# quadripod_v2.net
KiCad netlist of a schematic drawn in EAGLE
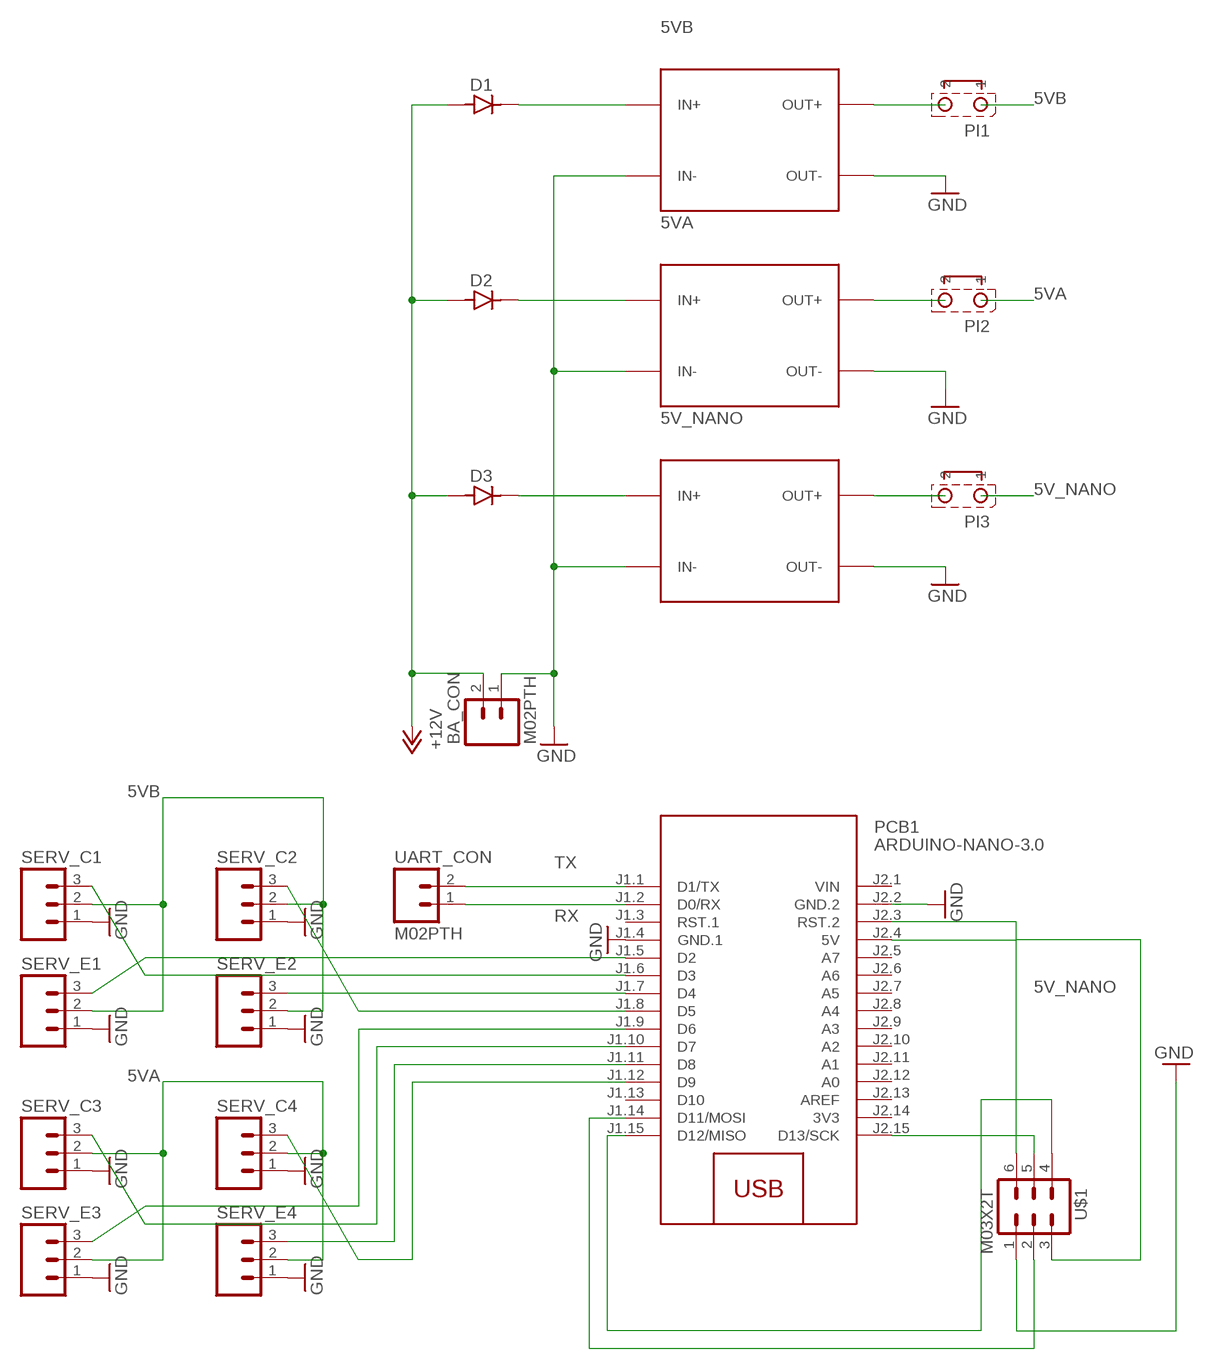
[diagram p0: schematic, sheet 1]

(export (version "E")
  (design (tool "Eeschema 10.0.6"))
  (components
    (comp (ref "5VA")
      (value "DC-DC-STEP-DOWN-LM2596")
      (footprint "eagle-import:DC-DC-STEP-DOWN-LM2596")
      (libsource (lib "eagle-import") (part "DC-DC-STEP-DOWN-LM2596"))
    )
    (comp (ref "5VB")
      (value "DC-DC-STEP-DOWN-LM2596")
      (footprint "eagle-import:DC-DC-STEP-DOWN-LM2596")
      (libsource (lib "eagle-import") (part "DC-DC-STEP-DOWN-LM2596"))
    )
    (comp (ref "5V_NANO")
      (value "DC-DC-STEP-DOWN-LM2596")
      (footprint "eagle-import:DC-DC-STEP-DOWN-LM2596")
      (libsource (lib "eagle-import") (part "DC-DC-STEP-DOWN-LM2596"))
    )
    (comp (ref "BA_CON")
      (value "M02PTH")
      (footprint "eagle-import:1X02")
      (libsource (lib "eagle-import") (part "M02PTH"))
    )
    (comp (ref "D1")
      (value "DIODES_DIODE/DO41")
      (footprint "eagle-import:DIODES_DO41")
      (libsource (lib "eagle-import") (part "DIODES_DIODE/DO41"))
    )
    (comp (ref "D2")
      (value "DIODES_DIODE/DO41")
      (footprint "eagle-import:DIODES_DO41")
      (libsource (lib "eagle-import") (part "DIODES_DIODE/DO41"))
    )
    (comp (ref "D3")
      (value "DIODES_DIODE/DO41")
      (footprint "eagle-import:DIODES_DO41")
      (libsource (lib "eagle-import") (part "DIODES_DIODE/DO41"))
    )
    (comp (ref "PCB1")
      (value "ARDUINO-NANO-3.0")
      (footprint "eagle-import:ARDUINO-NANO-3.0")
      (libsource (lib "eagle-import") (part "ARDUINO-NANO-3.0"))
    )
    (comp (ref "PI1")
      (value "STCMS_2")
      (footprint "eagle-import:STCMS_2")
      (libsource (lib "eagle-import") (part "STCMS_2"))
    )
    (comp (ref "PI2")
      (value "STCMS_2")
      (footprint "eagle-import:STCMS_2")
      (libsource (lib "eagle-import") (part "STCMS_2"))
    )
    (comp (ref "PI3")
      (value "STCMS_2")
      (footprint "eagle-import:STCMS_2")
      (libsource (lib "eagle-import") (part "STCMS_2"))
    )
    (comp (ref "SERV_C1")
      (value "M03LONGPADS")
      (footprint "eagle-import:1X03_LONGPADS")
      (libsource (lib "eagle-import") (part "M03LONGPADS"))
    )
    (comp (ref "SERV_C2")
      (value "M03LONGPADS")
      (footprint "eagle-import:1X03_LONGPADS")
      (libsource (lib "eagle-import") (part "M03LONGPADS"))
    )
    (comp (ref "SERV_C3")
      (value "M03LONGPADS")
      (footprint "eagle-import:1X03_LONGPADS")
      (libsource (lib "eagle-import") (part "M03LONGPADS"))
    )
    (comp (ref "SERV_C4")
      (value "M03LONGPADS")
      (footprint "eagle-import:1X03_LONGPADS")
      (libsource (lib "eagle-import") (part "M03LONGPADS"))
    )
    (comp (ref "SERV_E1")
      (value "M03LONGPADS")
      (footprint "eagle-import:1X03_LONGPADS")
      (libsource (lib "eagle-import") (part "M03LONGPADS"))
    )
    (comp (ref "SERV_E2")
      (value "M03LONGPADS")
      (footprint "eagle-import:1X03_LONGPADS")
      (libsource (lib "eagle-import") (part "M03LONGPADS"))
    )
    (comp (ref "SERV_E3")
      (value "M03LONGPADS")
      (footprint "eagle-import:1X03_LONGPADS")
      (libsource (lib "eagle-import") (part "M03LONGPADS"))
    )
    (comp (ref "SERV_E4")
      (value "M03LONGPADS")
      (footprint "eagle-import:1X03_LONGPADS")
      (libsource (lib "eagle-import") (part "M03LONGPADS"))
    )
    (comp (ref "U$1")
      (value "M03X2T")
      (footprint "eagle-import:2X03")
      (libsource (lib "eagle-import") (part "M03X2T"))
    )
    (comp (ref "UART_CON")
      (value "M02PTH")
      (footprint "eagle-import:1X02")
      (libsource (lib "eagle-import") (part "M02PTH"))
    )
  )
  (nets
    (net (code "1") (name "+12V") (class "Default")
      (node (ref "BA_CON") (pin "2") (pinfunction "2_2") (pintype "passive"))
      (node (ref "D1") (pin "A") (pinfunction "A_A") (pintype "passive"))
      (node (ref "D2") (pin "A") (pinfunction "A_A") (pintype "passive"))
      (node (ref "D3") (pin "A") (pinfunction "A_A") (pintype "passive"))
    )
    (net (code "2") (name "/3V3") (class "Default")
      (node (ref "PCB1") (pin "J2.14") (pinfunction "3V3_J2.14") (pintype "power_in"))
    )
    (net (code "3") (name "/5VA") (class "Default")
      (node (ref "PI2") (pin "1") (pinfunction "1_1") (pintype "bidirectional"))
      (node (ref "SERV_C3") (pin "2") (pinfunction "2_2") (pintype "passive"))
      (node (ref "SERV_C4") (pin "2") (pinfunction "2_2") (pintype "passive"))
      (node (ref "SERV_E3") (pin "2") (pinfunction "2_2") (pintype "passive"))
      (node (ref "SERV_E4") (pin "2") (pinfunction "2_2") (pintype "passive"))
    )
    (net (code "4") (name "/5VB") (class "Default")
      (node (ref "PI1") (pin "1") (pinfunction "1_1") (pintype "bidirectional"))
      (node (ref "SERV_C1") (pin "2") (pinfunction "2_2") (pintype "passive"))
      (node (ref "SERV_C2") (pin "2") (pinfunction "2_2") (pintype "passive"))
      (node (ref "SERV_E1") (pin "2") (pinfunction "2_2") (pintype "passive"))
      (node (ref "SERV_E2") (pin "2") (pinfunction "2_2") (pintype "passive"))
    )
    (net (code "5") (name "/5V_NANO") (class "Default")
      (node (ref "PCB1") (pin "J2.4") (pinfunction "5V_J2.4") (pintype "power_in"))
      (node (ref "PI3") (pin "1") (pinfunction "1_1") (pintype "bidirectional"))
      (node (ref "U$1") (pin "3") (pinfunction "3_3") (pintype "passive"))
    )
    (net (code "6") (name "/RX") (class "Default")
      (node (ref "PCB1") (pin "J1.2") (pinfunction "D0/RX_J1.2") (pintype "bidirectional"))
      (node (ref "UART_CON") (pin "1") (pinfunction "1_1") (pintype "passive"))
    )
    (net (code "7") (name "/TX") (class "Default")
      (node (ref "PCB1") (pin "J1.1") (pinfunction "D1/TX_J1.1") (pintype "bidirectional"))
      (node (ref "UART_CON") (pin "2") (pinfunction "2_2") (pintype "passive"))
    )
    (net (code "8") (name "/VIN") (class "Default")
      (node (ref "PCB1") (pin "J2.1") (pinfunction "VIN_J2.1") (pintype "power_in"))
    )
    (net (code "9") (name "GND") (class "Default")
      (node (ref "5VA") (pin "IN-") (pinfunction "IN-_IN-") (pintype "bidirectional"))
      (node (ref "5VA") (pin "OUT-") (pinfunction "OUT-_OUT-") (pintype "bidirectional"))
      (node (ref "5VB") (pin "IN-") (pinfunction "IN-_IN-") (pintype "bidirectional"))
      (node (ref "5VB") (pin "OUT-") (pinfunction "OUT-_OUT-") (pintype "bidirectional"))
      (node (ref "5V_NANO") (pin "IN-") (pinfunction "IN-_IN-") (pintype "bidirectional"))
      (node (ref "5V_NANO") (pin "OUT-") (pinfunction "OUT-_OUT-") (pintype "bidirectional"))
      (node (ref "BA_CON") (pin "1") (pinfunction "1_1") (pintype "passive"))
      (node (ref "PCB1") (pin "J1.4") (pinfunction "GND.1_J1.4") (pintype "power_in"))
      (node (ref "PCB1") (pin "J2.2") (pinfunction "GND.2_J2.2") (pintype "power_in"))
      (node (ref "SERV_C1") (pin "1") (pinfunction "1_1") (pintype "passive"))
      (node (ref "SERV_C2") (pin "1") (pinfunction "1_1") (pintype "passive"))
      (node (ref "SERV_C3") (pin "1") (pinfunction "1_1") (pintype "passive"))
      (node (ref "SERV_C4") (pin "1") (pinfunction "1_1") (pintype "passive"))
      (node (ref "SERV_E1") (pin "1") (pinfunction "1_1") (pintype "passive"))
      (node (ref "SERV_E2") (pin "1") (pinfunction "1_1") (pintype "passive"))
      (node (ref "SERV_E3") (pin "1") (pinfunction "1_1") (pintype "passive"))
      (node (ref "SERV_E4") (pin "1") (pinfunction "1_1") (pintype "passive"))
      (node (ref "U$1") (pin "1") (pinfunction "1_1") (pintype "passive"))
    )
    (net (code "10") (name "Net-(5VA-PadIN+)") (class "Default")
      (node (ref "5VA") (pin "IN+") (pinfunction "IN+_IN+") (pintype "bidirectional"))
      (node (ref "D2") (pin "K") (pinfunction "K_K") (pintype "passive"))
    )
    (net (code "11") (name "Net-(5VA-PadOUT+)") (class "Default")
      (node (ref "5VA") (pin "OUT+") (pinfunction "OUT+_OUT+") (pintype "bidirectional"))
      (node (ref "PI2") (pin "2") (pinfunction "2_2") (pintype "bidirectional"))
    )
    (net (code "12") (name "Net-(5VB-PadIN+)") (class "Default")
      (node (ref "5VB") (pin "IN+") (pinfunction "IN+_IN+") (pintype "bidirectional"))
      (node (ref "D1") (pin "K") (pinfunction "K_K") (pintype "passive"))
    )
    (net (code "13") (name "Net-(5VB-PadOUT+)") (class "Default")
      (node (ref "5VB") (pin "OUT+") (pinfunction "OUT+_OUT+") (pintype "bidirectional"))
      (node (ref "PI1") (pin "2") (pinfunction "2_2") (pintype "bidirectional"))
    )
    (net (code "14") (name "Net-(5V_NANO-PadIN+)") (class "Default")
      (node (ref "5V_NANO") (pin "IN+") (pinfunction "IN+_IN+") (pintype "bidirectional"))
      (node (ref "D3") (pin "K") (pinfunction "K_K") (pintype "passive"))
    )
    (net (code "15") (name "Net-(5V_NANO-PadOUT+)") (class "Default")
      (node (ref "5V_NANO") (pin "OUT+") (pinfunction "OUT+_OUT+") (pintype "bidirectional"))
      (node (ref "PI3") (pin "2") (pinfunction "2_2") (pintype "bidirectional"))
    )
    (net (code "16") (name "Net-(PCB1-D2)") (class "Default")
      (node (ref "PCB1") (pin "J1.5") (pinfunction "D2_J1.5") (pintype "bidirectional"))
      (node (ref "SERV_E1") (pin "3") (pinfunction "3_3") (pintype "passive"))
    )
    (net (code "17") (name "Net-(PCB1-D3)") (class "Default")
      (node (ref "PCB1") (pin "J1.6") (pinfunction "D3_J1.6") (pintype "bidirectional"))
      (node (ref "SERV_C1") (pin "3") (pinfunction "3_3") (pintype "passive"))
    )
    (net (code "18") (name "Net-(PCB1-D4)") (class "Default")
      (node (ref "PCB1") (pin "J1.7") (pinfunction "D4_J1.7") (pintype "bidirectional"))
      (node (ref "SERV_E2") (pin "3") (pinfunction "3_3") (pintype "passive"))
    )
    (net (code "19") (name "Net-(PCB1-D5)") (class "Default")
      (node (ref "PCB1") (pin "J1.8") (pinfunction "D5_J1.8") (pintype "bidirectional"))
      (node (ref "SERV_C2") (pin "3") (pinfunction "3_3") (pintype "passive"))
    )
    (net (code "20") (name "Net-(PCB1-D6)") (class "Default")
      (node (ref "PCB1") (pin "J1.9") (pinfunction "D6_J1.9") (pintype "bidirectional"))
      (node (ref "SERV_E3") (pin "3") (pinfunction "3_3") (pintype "passive"))
    )
    (net (code "21") (name "Net-(PCB1-D7)") (class "Default")
      (node (ref "PCB1") (pin "J1.10") (pinfunction "D7_J1.10") (pintype "bidirectional"))
      (node (ref "SERV_C3") (pin "3") (pinfunction "3_3") (pintype "passive"))
    )
    (net (code "22") (name "Net-(PCB1-D8)") (class "Default")
      (node (ref "PCB1") (pin "J1.11") (pinfunction "D8_J1.11") (pintype "bidirectional"))
      (node (ref "SERV_E4") (pin "3") (pinfunction "3_3") (pintype "passive"))
    )
    (net (code "23") (name "Net-(PCB1-D9)") (class "Default")
      (node (ref "PCB1") (pin "J1.12") (pinfunction "D9_J1.12") (pintype "bidirectional"))
      (node (ref "SERV_C4") (pin "3") (pinfunction "3_3") (pintype "passive"))
    )
    (net (code "24") (name "Net-(PCB1-D11{slash}MOSI)") (class "Default")
      (node (ref "PCB1") (pin "J1.14") (pinfunction "D11/MOSI_J1.14") (pintype "bidirectional"))
      (node (ref "U$1") (pin "2") (pinfunction "2_2") (pintype "passive"))
    )
    (net (code "25") (name "Net-(PCB1-D12{slash}MISO)") (class "Default")
      (node (ref "PCB1") (pin "J1.15") (pinfunction "D12/MISO_J1.15") (pintype "bidirectional"))
      (node (ref "U$1") (pin "4") (pinfunction "4_4") (pintype "passive"))
    )
    (net (code "26") (name "Net-(PCB1-D13{slash}SCK)") (class "Default")
      (node (ref "PCB1") (pin "J2.15") (pinfunction "D13/SCK_J2.15") (pintype "bidirectional"))
      (node (ref "U$1") (pin "5") (pinfunction "5_5") (pintype "passive"))
    )
    (net (code "27") (name "Net-(PCB1-RST.2)") (class "Default")
      (node (ref "PCB1") (pin "J2.3") (pinfunction "RST.2_J2.3") (pintype "bidirectional"))
      (node (ref "U$1") (pin "6") (pinfunction "6_6") (pintype "passive"))
    )
    (net (code "28") (name "unconnected-(PCB1-A0-PadJ2.12)") (class "Default")
      (node (ref "PCB1") (pin "J2.12") (pinfunction "A0_J2.12") (pintype "bidirectional"))
    )
    (net (code "29") (name "unconnected-(PCB1-A1-PadJ2.11)") (class "Default")
      (node (ref "PCB1") (pin "J2.11") (pinfunction "A1_J2.11") (pintype "bidirectional"))
    )
    (net (code "30") (name "unconnected-(PCB1-A2-PadJ2.10)") (class "Default")
      (node (ref "PCB1") (pin "J2.10") (pinfunction "A2_J2.10") (pintype "bidirectional"))
    )
    (net (code "31") (name "unconnected-(PCB1-A3-PadJ2.9)") (class "Default")
      (node (ref "PCB1") (pin "J2.9") (pinfunction "A3_J2.9") (pintype "bidirectional"))
    )
    (net (code "32") (name "unconnected-(PCB1-A4-PadJ2.8)") (class "Default")
      (node (ref "PCB1") (pin "J2.8") (pinfunction "A4_J2.8") (pintype "bidirectional"))
    )
    (net (code "33") (name "unconnected-(PCB1-A5-PadJ2.7)") (class "Default")
      (node (ref "PCB1") (pin "J2.7") (pinfunction "A5_J2.7") (pintype "bidirectional"))
    )
    (net (code "34") (name "unconnected-(PCB1-A6-PadJ2.6)") (class "Default")
      (node (ref "PCB1") (pin "J2.6") (pinfunction "A6_J2.6") (pintype "bidirectional"))
    )
    (net (code "35") (name "unconnected-(PCB1-A7-PadJ2.5)") (class "Default")
      (node (ref "PCB1") (pin "J2.5") (pinfunction "A7_J2.5") (pintype "bidirectional"))
    )
    (net (code "36") (name "unconnected-(PCB1-AREF-PadJ2.13)") (class "Default")
      (node (ref "PCB1") (pin "J2.13") (pinfunction "AREF_J2.13") (pintype "bidirectional"))
    )
    (net (code "37") (name "unconnected-(PCB1-D10-PadJ1.13)") (class "Default")
      (node (ref "PCB1") (pin "J1.13") (pinfunction "D10_J1.13") (pintype "bidirectional"))
    )
    (net (code "38") (name "unconnected-(PCB1-RST.1-PadJ1.3)") (class "Default")
      (node (ref "PCB1") (pin "J1.3") (pinfunction "RST.1_J1.3") (pintype "bidirectional"))
    )
  )
)
